# Sheet1.net
KiCad netlist of a schematic drawn in Altium Designer
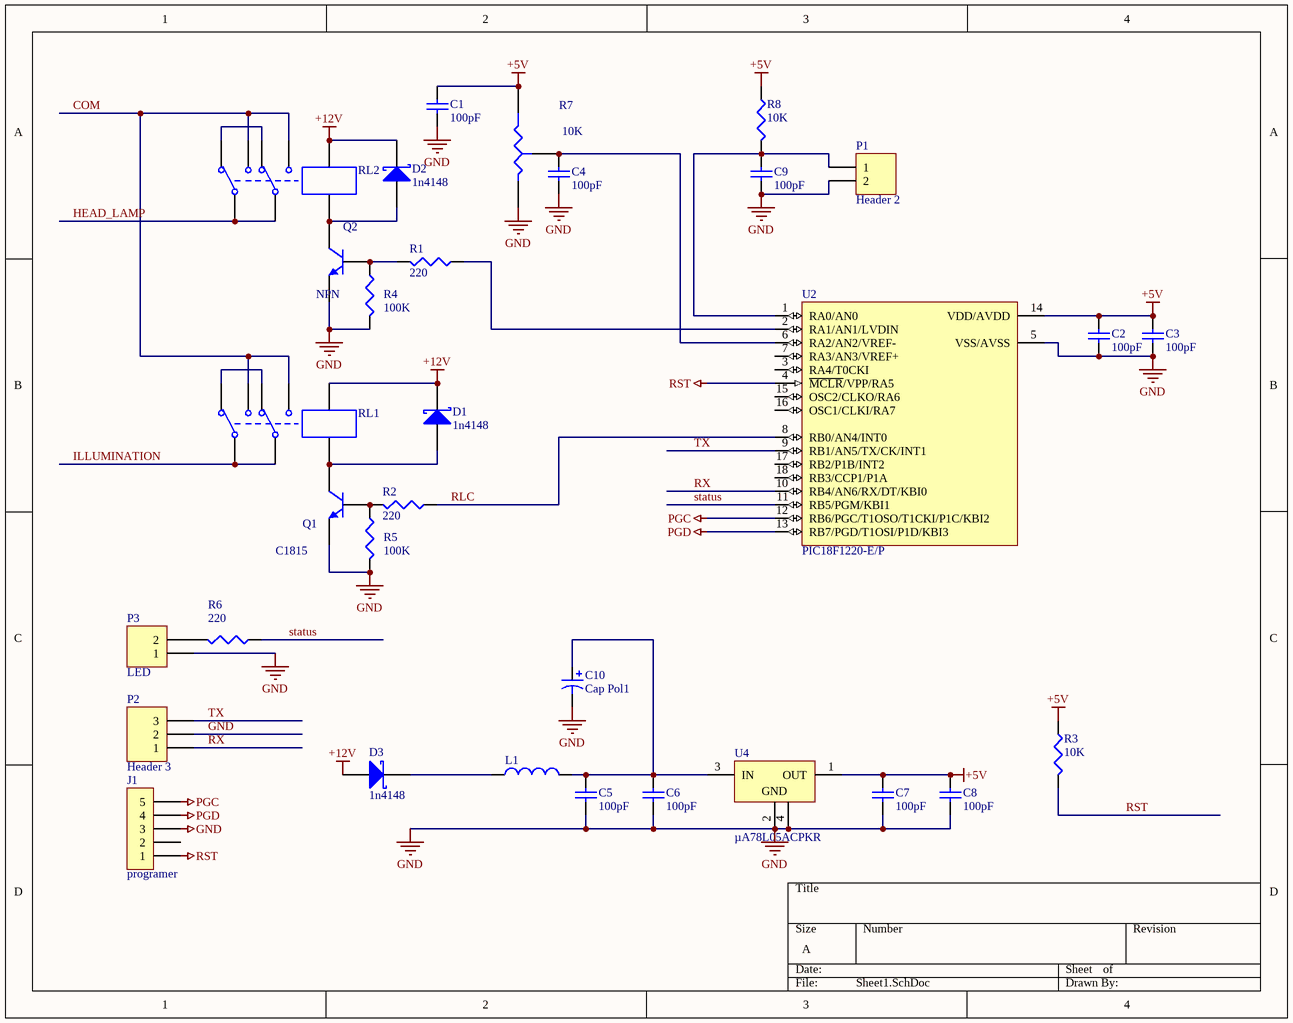
[diagram p0: Sheet1.SchDoc]

(export (version "E")
  (design (tool "Eeschema 10.0.6"))
  (components
    (comp (ref "C1")
      (value "100pF")
      (footprint "RESC2012L")
      (description "Capacitor (Semiconductor SIM Model)")
      (fields (field (name "Comment") "Cap Semi") (field (name "PUBLISHER") "Altium Limited"))
      (libsource (lib "Miscellaneous Devices") (part "Cap Semi"))
    )
    (comp (ref "C2")
      (value "100pF")
      (footprint "RESC2012L")
      (description "Capacitor (Semiconductor SIM Model)")
      (fields (field (name "Comment") "Cap Semi") (field (name "PUBLISHER") "Altium Limited"))
      (libsource (lib "Miscellaneous Devices") (part "Cap Semi"))
    )
    (comp (ref "C3")
      (value "100pF")
      (footprint "RESC2012L")
      (description "Capacitor (Semiconductor SIM Model)")
      (fields (field (name "Comment") "Cap Semi") (field (name "PUBLISHER") "Altium Limited"))
      (libsource (lib "Miscellaneous Devices") (part "Cap Semi"))
    )
    (comp (ref "C4")
      (value "100pF")
      (footprint "RESC2012L")
      (description "Capacitor (Semiconductor SIM Model)")
      (fields (field (name "Comment") "Cap Semi") (field (name "PUBLISHER") "Altium Limited"))
      (libsource (lib "Miscellaneous Devices") (part "Cap Semi"))
    )
    (comp (ref "C5")
      (value "100pF")
      (footprint "RESC2012L")
      (description "Capacitor (Semiconductor SIM Model)")
      (fields (field (name "Comment") "Cap Semi") (field (name "PUBLISHER") "Altium Limited"))
      (libsource (lib "Miscellaneous Devices") (part "Cap Semi"))
    )
    (comp (ref "C6")
      (value "100pF")
      (footprint "RESC2012L")
      (description "Capacitor (Semiconductor SIM Model)")
      (fields (field (name "Comment") "Cap Semi") (field (name "PUBLISHER") "Altium Limited"))
      (libsource (lib "Miscellaneous Devices") (part "Cap Semi"))
    )
    (comp (ref "C7")
      (value "100pF")
      (footprint "RESC2012L")
      (description "Capacitor (Semiconductor SIM Model)")
      (fields (field (name "Comment") "Cap Semi") (field (name "PUBLISHER") "Altium Limited"))
      (libsource (lib "Miscellaneous Devices") (part "Cap Semi"))
    )
    (comp (ref "C8")
      (value "100pF")
      (footprint "RESC2012L")
      (description "Capacitor (Semiconductor SIM Model)")
      (fields (field (name "Comment") "Cap Semi") (field (name "PUBLISHER") "Altium Limited"))
      (libsource (lib "Miscellaneous Devices") (part "Cap Semi"))
    )
    (comp (ref "C9")
      (value "100pF")
      (footprint "RESC2012L")
      (description "Capacitor (Semiconductor SIM Model)")
      (fields (field (name "Comment") "Cap Semi") (field (name "PUBLISHER") "Altium Limited"))
      (libsource (lib "Miscellaneous Devices") (part "Cap Semi"))
    )
    (comp (ref "C10")
      (value "Cap Pol1")
      (footprint "CAP5")
      (description "Polarized Capacitor (Radial)")
      (fields (field (name "PUBLISHER") "Altium Limited"))
      (libsource (lib "Miscellaneous Devices") (part "Cap Pol1"))
    )
    (comp (ref "D1")
      (value "1n4148")
      (footprint "MELF-D5022-2009")
      (description "Schottky Diode")
      (fields (field (name "PUBLISHER") "Altium Limited"))
      (libsource (lib "Schlib1") (part "1N4148_SMD"))
    )
    (comp (ref "D2")
      (value "1n4148")
      (footprint "MELF-D5022-2009")
      (description "Schottky Diode")
      (fields (field (name "PUBLISHER") "Altium Limited"))
      (libsource (lib "Schlib1") (part "1N4148_SMD"))
    )
    (comp (ref "D3")
      (value "1n4148")
      (footprint "MELF-D5022-2009")
      (description "Schottky Diode")
      (fields (field (name "PUBLISHER") "Altium Limited"))
      (libsource (lib "Schlib1") (part "1N4148_SMD"))
    )
    (comp (ref "J1")
      (value "programer")
      (footprint "HDR1x5")
      (description "Connector")
      (libsource (lib "*") (part "CON5"))
    )
    (comp (ref "L1")
      (value "~")
      (footprint "INDC3216")
      (description "Inductor")
      (fields (field (name "PUBLISHER") "Altium Limited"))
      (libsource (lib "Miscellaneous Devices") (part "Inductor"))
    )
    (comp (ref "P1")
      (value "Header 2")
      (footprint "HDR1X2")
      (description "Header, 2-Pin")
      (fields (field (name "PUBLISHER") "Altium Limited"))
      (libsource (lib "Miscellaneous Connectors") (part "Header 2"))
    )
    (comp (ref "P2")
      (value "Header 3")
      (footprint "HDR1X3")
      (description "Header, 3-Pin")
      (fields (field (name "PUBLISHER") "Altium Limited"))
      (libsource (lib "Miscellaneous Connectors") (part "Header 3"))
    )
    (comp (ref "P3")
      (value "LED")
      (footprint "HDR1X2")
      (description "Header, 2-Pin")
      (fields (field (name "PUBLISHER") "Altium Limited"))
      (libsource (lib "") (part "Header 2_1"))
    )
    (comp (ref "Q1")
      (value "C1815")
      (footprint "SOT-23B")
      (description "NPN Bipolar Transistor")
      (fields (field (name "PUBLISHER") "Altium Limited"))
      (libsource (lib "Miscellaneous Devices") (part "NPN"))
    )
    (comp (ref "Q2")
      (value "NPN")
      (footprint "SOT-23B")
      (description "NPN Bipolar Transistor")
      (fields (field (name "PUBLISHER") "Altium Limited"))
      (libsource (lib "Miscellaneous Devices") (part "NPN"))
    )
    (comp (ref "R1")
      (value "220")
      (footprint "RESC2012L")
      (description "Resistor")
      (fields (field (name "Comment") "Res3") (field (name "PUBLISHER") "Altium Limited"))
      (libsource (lib "Miscellaneous Devices") (part "Res3"))
    )
    (comp (ref "R2")
      (value "220")
      (footprint "RESC2012L")
      (description "Resistor")
      (fields (field (name "Comment") "Res3") (field (name "PUBLISHER") "Altium Limited"))
      (libsource (lib "Miscellaneous Devices") (part "Res3"))
    )
    (comp (ref "R3")
      (value "10K")
      (footprint "RESC2012L")
      (description "Resistor")
      (fields (field (name "Comment") "Res3") (field (name "PUBLISHER") "Altium Limited"))
      (libsource (lib "Miscellaneous Devices") (part "Res3"))
    )
    (comp (ref "R4")
      (value "100K")
      (footprint "RESC2012L")
      (description "Resistor")
      (fields (field (name "Comment") "Res3") (field (name "PUBLISHER") "Altium Limited"))
      (libsource (lib "Miscellaneous Devices") (part "Res3"))
    )
    (comp (ref "R5")
      (value "100K")
      (footprint "RESC2012L")
      (description "Resistor")
      (fields (field (name "Comment") "Res3") (field (name "PUBLISHER") "Altium Limited"))
      (libsource (lib "Miscellaneous Devices") (part "Res3"))
    )
    (comp (ref "R6")
      (value "220")
      (footprint "RESC2012L")
      (description "Resistor")
      (fields (field (name "Comment") "Res3") (field (name "PUBLISHER") "Altium Limited"))
      (libsource (lib "Miscellaneous Devices") (part "Res3"))
    )
    (comp (ref "R7")
      (value "10K")
      (footprint "VR_V_MH")
      (description "Tapped Resistor")
      (fields (field (name "Comment") "Res Tap") (field (name "PUBLISHER") "Altium Limited"))
      (libsource (lib "Miscellaneous Devices") (part "Res Tap"))
    )
    (comp (ref "R8")
      (value "10K")
      (footprint "RESC2012L")
      (description "Resistor")
      (fields (field (name "Comment") "Res3") (field (name "PUBLISHER") "Altium Limited"))
      (libsource (lib "Miscellaneous Devices") (part "Res3"))
    )
    (comp (ref "RL1")
      (value "Relay-DPDT")
      (footprint "RELAY_8PIN_MH")
      (description "Dual-Pole Dual-Throw Relay")
      (fields (field (name "PUBLISHER") "Altium Limited"))
      (libsource (lib "Miscellaneous Devices") (part "Relay-DPDT"))
    )
    (comp (ref "RL2")
      (value "Relay-DPDT")
      (footprint "RELAY_8PIN_MH")
      (description "Dual-Pole Dual-Throw Relay")
      (fields (field (name "PUBLISHER") "Altium Limited"))
      (libsource (lib "Miscellaneous Devices") (part "Relay-DPDT"))
    )
    (comp (ref "U2")
      (value "PIC18F1220-E/P")
      (footprint "PDIP300-P18")
      (fields (field (name "PUBLISHER") "Altium Limited"))
      (libsource (lib "Microchip Microcontroller 8-Bit PIC18") (part "PIC18F1220-E/P"))
    )
    (comp (ref "U4")
      (value "µA78L05ACPKR")
      (footprint "PK03")
      (description "Positive-Voltage Regulator")
      (fields (field (name "PUBLISHER") "Altium Limited"))
      (libsource (lib "Schlib1") (part "µA78L05ACPKR"))
    )
  )
  (nets
    (net (code "1") (name "+5V") (class "Default")
      (node (ref "C1") (pin "2") (pinfunction "2_2") (pintype "passive"))
      (node (ref "C2") (pin "2") (pinfunction "2_2") (pintype "passive"))
      (node (ref "C3") (pin "2") (pinfunction "2_2") (pintype "passive"))
      (node (ref "C7") (pin "2") (pinfunction "2_2") (pintype "passive"))
      (node (ref "C8") (pin "2") (pinfunction "2_2") (pintype "passive"))
      (node (ref "R3") (pin "1") (pinfunction "1_1") (pintype "passive"))
      (node (ref "R7") (pin "2") (pinfunction "B_2") (pintype "passive"))
      (node (ref "R8") (pin "1") (pinfunction "1_1") (pintype "passive"))
      (node (ref "U2") (pin "14") (pinfunction "VDD/AVDD_14") (pintype "power_in"))
      (node (ref "U4") (pin "1") (pinfunction "OUT_1") (pintype "power_in"))
    )
    (net (code "2") (name "+12V") (class "Default")
      (node (ref "D1") (pin "2") (pinfunction "K_2") (pintype "passive"))
      (node (ref "D2") (pin "2") (pinfunction "K_2") (pintype "passive"))
      (node (ref "D3") (pin "1") (pinfunction "A_1") (pintype "passive"))
      (node (ref "RL1") (pin "8") (pinfunction "8_8") (pintype "passive"))
      (node (ref "RL2") (pin "8") (pinfunction "8_8") (pintype "passive"))
    )
    (net (code "3") (name "/COM") (class "Default")
      (node (ref "RL1") (pin "3") (pinfunction "3_3") (pintype "passive"))
      (node (ref "RL1") (pin "6") (pinfunction "6_6") (pintype "passive"))
      (node (ref "RL2") (pin "3") (pinfunction "3_3") (pintype "passive"))
      (node (ref "RL2") (pin "6") (pinfunction "6_6") (pintype "passive"))
    )
    (net (code "4") (name "/HEAD_LAMP") (class "Default")
      (node (ref "RL2") (pin "1") (pinfunction "1_1") (pintype "passive"))
      (node (ref "RL2") (pin "4") (pinfunction "4_4") (pintype "passive"))
    )
    (net (code "5") (name "/ILLUMINATION") (class "Default")
      (node (ref "RL1") (pin "1") (pinfunction "1_1") (pintype "passive"))
      (node (ref "RL1") (pin "4") (pinfunction "4_4") (pintype "passive"))
    )
    (net (code "6") (name "/RLC") (class "Default")
      (node (ref "R2") (pin "1") (pinfunction "1_1") (pintype "passive"))
      (node (ref "U2") (pin "8") (pinfunction "RB0/AN4/INT0_8") (pintype "bidirectional"))
    )
    (net (code "7") (name "/RX") (class "Default")
      (node (ref "P2") (pin "1") (pinfunction "1_1") (pintype "passive"))
      (node (ref "U2") (pin "10") (pinfunction "RB4/AN6/RX/DT/KBI0_10") (pintype "bidirectional"))
    )
    (net (code "8") (name "/TX") (class "Default")
      (node (ref "P2") (pin "3") (pinfunction "3_3") (pintype "passive"))
      (node (ref "U2") (pin "9") (pinfunction "RB1/AN5/TX/CK/INT1_9") (pintype "bidirectional"))
    )
    (net (code "9") (name "/status") (class "Default")
      (node (ref "R6") (pin "1") (pinfunction "1_1") (pintype "passive"))
      (node (ref "U2") (pin "11") (pinfunction "RB5/PGM/KBI1_11") (pintype "bidirectional"))
    )
    (net (code "10") (name "GND") (class "Default")
      (node (ref "C1") (pin "1") (pinfunction "1_1") (pintype "passive"))
      (node (ref "C10") (pin "2") (pinfunction "2_2") (pintype "passive"))
      (node (ref "C2") (pin "1") (pinfunction "1_1") (pintype "passive"))
      (node (ref "C3") (pin "1") (pinfunction "1_1") (pintype "passive"))
      (node (ref "C4") (pin "1") (pinfunction "1_1") (pintype "passive"))
      (node (ref "C5") (pin "1") (pinfunction "1_1") (pintype "passive"))
      (node (ref "C6") (pin "1") (pinfunction "1_1") (pintype "passive"))
      (node (ref "C7") (pin "1") (pinfunction "1_1") (pintype "passive"))
      (node (ref "C8") (pin "1") (pinfunction "1_1") (pintype "passive"))
      (node (ref "C9") (pin "1") (pinfunction "1_1") (pintype "passive"))
      (node (ref "J1") (pin "3") (pinfunction "3_3") (pintype "passive"))
      (node (ref "P1") (pin "2") (pinfunction "2_2") (pintype "passive"))
      (node (ref "P2") (pin "2") (pinfunction "2_2") (pintype "passive"))
      (node (ref "P3") (pin "1") (pinfunction "1_1") (pintype "passive"))
      (node (ref "Q1") (pin "3") (pinfunction "E_3") (pintype "passive"))
      (node (ref "Q2") (pin "3") (pinfunction "E_3") (pintype "passive"))
      (node (ref "R4") (pin "2") (pinfunction "2_2") (pintype "passive"))
      (node (ref "R5") (pin "2") (pinfunction "2_2") (pintype "passive"))
      (node (ref "R7") (pin "1") (pinfunction "A_1") (pintype "passive"))
      (node (ref "U2") (pin "5") (pinfunction "VSS/AVSS_5") (pintype "power_in"))
      (node (ref "U4") (pin "2") (pinfunction "GND_2") (pintype "power_in"))
      (node (ref "U4") (pin "4") (pinfunction "GND_4") (pintype "power_in"))
    )
    (net (code "11") (name "Net-(D1-A)") (class "Default")
      (node (ref "D1") (pin "1") (pinfunction "A_1") (pintype "passive"))
      (node (ref "Q1") (pin "1") (pinfunction "C_1") (pintype "passive"))
      (node (ref "RL1") (pin "7") (pinfunction "7_7") (pintype "passive"))
    )
    (net (code "12") (name "Net-(D2-A)") (class "Default")
      (node (ref "D2") (pin "1") (pinfunction "A_1") (pintype "passive"))
      (node (ref "Q2") (pin "1") (pinfunction "C_1") (pintype "passive"))
      (node (ref "RL2") (pin "7") (pinfunction "7_7") (pintype "passive"))
    )
    (net (code "13") (name "Net-(D3-K)") (class "Default")
      (node (ref "D3") (pin "2") (pinfunction "K_2") (pintype "passive"))
      (node (ref "L1") (pin "1") (pinfunction "1_1") (pintype "passive"))
    )
    (net (code "14") (name "Net-(P3-Pad2)") (class "Default")
      (node (ref "P3") (pin "2") (pinfunction "2_2") (pintype "passive"))
      (node (ref "R6") (pin "2") (pinfunction "2_2") (pintype "passive"))
    )
    (net (code "15") (name "Net-(Q1-B)") (class "Default")
      (node (ref "Q1") (pin "2") (pinfunction "B_2") (pintype "passive"))
      (node (ref "R2") (pin "2") (pinfunction "2_2") (pintype "passive"))
      (node (ref "R5") (pin "1") (pinfunction "1_1") (pintype "passive"))
    )
    (net (code "16") (name "Net-(Q2-B)") (class "Default")
      (node (ref "Q2") (pin "2") (pinfunction "B_2") (pintype "passive"))
      (node (ref "R1") (pin "2") (pinfunction "2_2") (pintype "passive"))
      (node (ref "R4") (pin "1") (pinfunction "1_1") (pintype "passive"))
    )
    (net (code "17") (name "Net-(R7-TAP)") (class "Default")
      (node (ref "C4") (pin "2") (pinfunction "2_2") (pintype "passive"))
      (node (ref "R7") (pin "3") (pinfunction "TAP_3") (pintype "passive"))
      (node (ref "U2") (pin "6") (pinfunction "RA2/AN2/VREF-_6") (pintype "bidirectional"))
    )
    (net (code "18") (name "Net-(RL1-Pad2)") (class "Default")
      (node (ref "RL1") (pin "2") (pinfunction "2_2") (pintype "passive"))
      (node (ref "RL1") (pin "5") (pinfunction "5_5") (pintype "passive"))
    )
    (net (code "19") (name "Net-(RL2-Pad2)") (class "Default")
      (node (ref "RL2") (pin "2") (pinfunction "2_2") (pintype "passive"))
      (node (ref "RL2") (pin "5") (pinfunction "5_5") (pintype "passive"))
    )
    (net (code "20") (name "Net-(U2-RA0{slash}AN0)") (class "Default")
      (node (ref "C9") (pin "2") (pinfunction "2_2") (pintype "passive"))
      (node (ref "P1") (pin "1") (pinfunction "1_1") (pintype "passive"))
      (node (ref "R8") (pin "2") (pinfunction "2_2") (pintype "passive"))
      (node (ref "U2") (pin "1") (pinfunction "RA0/AN0_1") (pintype "bidirectional"))
    )
    (net (code "21") (name "Net-(U2-RA1{slash}AN1{slash}LVDIN)") (class "Default")
      (node (ref "R1") (pin "1") (pinfunction "1_1") (pintype "passive"))
      (node (ref "U2") (pin "2") (pinfunction "RA1/AN1/LVDIN_2") (pintype "bidirectional"))
    )
    (net (code "22") (name "Net-(U4-IN)") (class "Default")
      (node (ref "C10") (pin "1") (pinfunction "1_1") (pintype "passive"))
      (node (ref "C5") (pin "2") (pinfunction "2_2") (pintype "passive"))
      (node (ref "C6") (pin "2") (pinfunction "2_2") (pintype "passive"))
      (node (ref "L1") (pin "2") (pinfunction "2_2") (pintype "passive"))
      (node (ref "U4") (pin "3") (pinfunction "IN_3") (pintype "power_in"))
    )
    (net (code "23") (name "PGC") (class "Default")
      (node (ref "J1") (pin "5") (pinfunction "5_5") (pintype "passive"))
      (node (ref "U2") (pin "12") (pinfunction "RB6/PGC/T1OSO/T1CKI/P1C/KBI2_12") (pintype "bidirectional"))
    )
    (net (code "24") (name "PGD") (class "Default")
      (node (ref "J1") (pin "4") (pinfunction "4_4") (pintype "passive"))
      (node (ref "U2") (pin "13") (pinfunction "RB7/PGD/T1OSI/P1D/KBI3_13") (pintype "bidirectional"))
    )
    (net (code "25") (name "RST") (class "Default")
      (node (ref "J1") (pin "1") (pinfunction "1_1") (pintype "passive"))
      (node (ref "R3") (pin "2") (pinfunction "2_2") (pintype "passive"))
      (node (ref "U2") (pin "4") (pinfunction "~{MCLR}/VPP/RA5_4") (pintype "input"))
    )
    (net (code "26") (name "unconnected-(J1-Pad2)") (class "Default")
      (node (ref "J1") (pin "2") (pinfunction "2_2") (pintype "passive"))
    )
    (net (code "27") (name "unconnected-(U2-OSC1{slash}CLKI{slash}RA7-Pad16)") (class "Default")
      (node (ref "U2") (pin "16") (pinfunction "OSC1/CLKI/RA7_16") (pintype "bidirectional"))
    )
    (net (code "28") (name "unconnected-(U2-OSC2{slash}CLKO{slash}RA6-Pad15)") (class "Default")
      (node (ref "U2") (pin "15") (pinfunction "OSC2/CLKO/RA6_15") (pintype "bidirectional"))
    )
    (net (code "29") (name "unconnected-(U2-RA3{slash}AN3{slash}VREF+-Pad7)") (class "Default")
      (node (ref "U2") (pin "7") (pinfunction "RA3/AN3/VREF+_7") (pintype "bidirectional"))
    )
    (net (code "30") (name "unconnected-(U2-RA4{slash}T0CKI-Pad3)") (class "Default")
      (node (ref "U2") (pin "3") (pinfunction "RA4/T0CKI_3") (pintype "bidirectional"))
    )
    (net (code "31") (name "unconnected-(U2-RB2{slash}P1B{slash}INT2-Pad17)") (class "Default")
      (node (ref "U2") (pin "17") (pinfunction "RB2/P1B/INT2_17") (pintype "bidirectional"))
    )
    (net (code "32") (name "unconnected-(U2-RB3{slash}CCP1{slash}P1A-Pad18)") (class "Default")
      (node (ref "U2") (pin "18") (pinfunction "RB3/CCP1/P1A_18") (pintype "bidirectional"))
    )
  )
)
